# equail.net
KiCad netlist of a schematic drawn in EAGLE
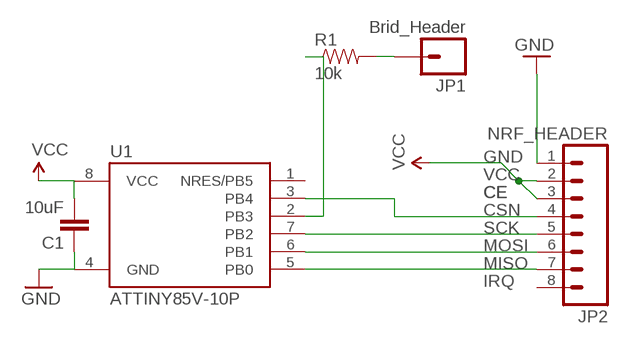
[diagram p0: schematic, sheet 1]

(export (version "E")
  (design (tool "Eeschema 10.0.6"))
  (components
    (comp (ref "C1")
      (value "10uF")
      (footprint "eagle-import:CAP-PTH-SMALLEZ")
      (libsource (lib "eagle-import") (part "CAPEZ"))
    )
    (comp (ref "JP1")
      (value "Brid_Header")
      (footprint "eagle-import:1X01")
      (libsource (lib "eagle-import") (part "M01PTH"))
    )
    (comp (ref "JP2")
      (value "NRF_HEADER")
      (footprint "eagle-import:1X08_PIN1_NO_SILK")
      (libsource (lib "eagle-import") (part "M08"))
    )
    (comp (ref "R1")
      (value "10k")
      (footprint "eagle-import:1_6W-RES")
      (libsource (lib "eagle-import") (part "RESISTORPTH-1/6W"))
    )
    (comp (ref "U1")
      (value "ATTINY85V-10P")
      (footprint "eagle-import:PDIP08_300MIL")
      (libsource (lib "eagle-import") (part "ATTINY85PV-10"))
    )
  )
  (nets
    (net (code "1") (name "GND") (class "Default")
      (node (ref "C1") (pin "1") (pinfunction "1_1") (pintype "passive"))
      (node (ref "JP2") (pin "1") (pinfunction "1_1") (pintype "passive"))
      (node (ref "U1") (pin "4") (pinfunction "GND_4") (pintype "power_in"))
    )
    (net (code "2") (name "Net-(JP1-Pad1)") (class "Default")
      (node (ref "JP1") (pin "1") (pinfunction "1_1") (pintype "passive"))
      (node (ref "R1") (pin "2") (pinfunction "2_2") (pintype "passive"))
    )
    (net (code "3") (name "Net-(U1-PB0)") (class "Default")
      (node (ref "JP2") (pin "7") (pinfunction "7_7") (pintype "passive"))
      (node (ref "U1") (pin "5") (pinfunction "PB0_5") (pintype "bidirectional"))
    )
    (net (code "4") (name "Net-(U1-PB1)") (class "Default")
      (node (ref "JP2") (pin "6") (pinfunction "6_6") (pintype "passive"))
      (node (ref "U1") (pin "6") (pinfunction "PB1_6") (pintype "bidirectional"))
    )
    (net (code "5") (name "Net-(U1-PB2)") (class "Default")
      (node (ref "JP2") (pin "5") (pinfunction "5_5") (pintype "passive"))
      (node (ref "U1") (pin "7") (pinfunction "PB2_7") (pintype "bidirectional"))
    )
    (net (code "6") (name "Net-(U1-PB3)") (class "Default")
      (node (ref "R1") (pin "1") (pinfunction "1_1") (pintype "passive"))
      (node (ref "U1") (pin "2") (pinfunction "PB3_2") (pintype "bidirectional"))
    )
    (net (code "7") (name "Net-(U1-PB4)") (class "Default")
      (node (ref "JP2") (pin "4") (pinfunction "4_4") (pintype "passive"))
      (node (ref "U1") (pin "3") (pinfunction "PB4_3") (pintype "bidirectional"))
    )
    (net (code "8") (name "VCC") (class "Default")
      (node (ref "C1") (pin "2") (pinfunction "2_2") (pintype "passive"))
      (node (ref "JP2") (pin "2") (pinfunction "2_2") (pintype "passive"))
      (node (ref "JP2") (pin "3") (pinfunction "3_3") (pintype "passive"))
      (node (ref "U1") (pin "8") (pinfunction "VCC_8") (pintype "power_in"))
    )
    (net (code "9") (name "unconnected-(JP2-Pad8)") (class "Default")
      (node (ref "JP2") (pin "8") (pinfunction "8_8") (pintype "passive"))
    )
    (net (code "10") (name "unconnected-(U1-NRES{slash}PB5-Pad1)") (class "Default")
      (node (ref "U1") (pin "1") (pinfunction "NRES/PB5_1") (pintype "bidirectional"))
    )
  )
)
